# TrinketBlinkM0G.net
KiCad netlist of a schematic drawn in EAGLE
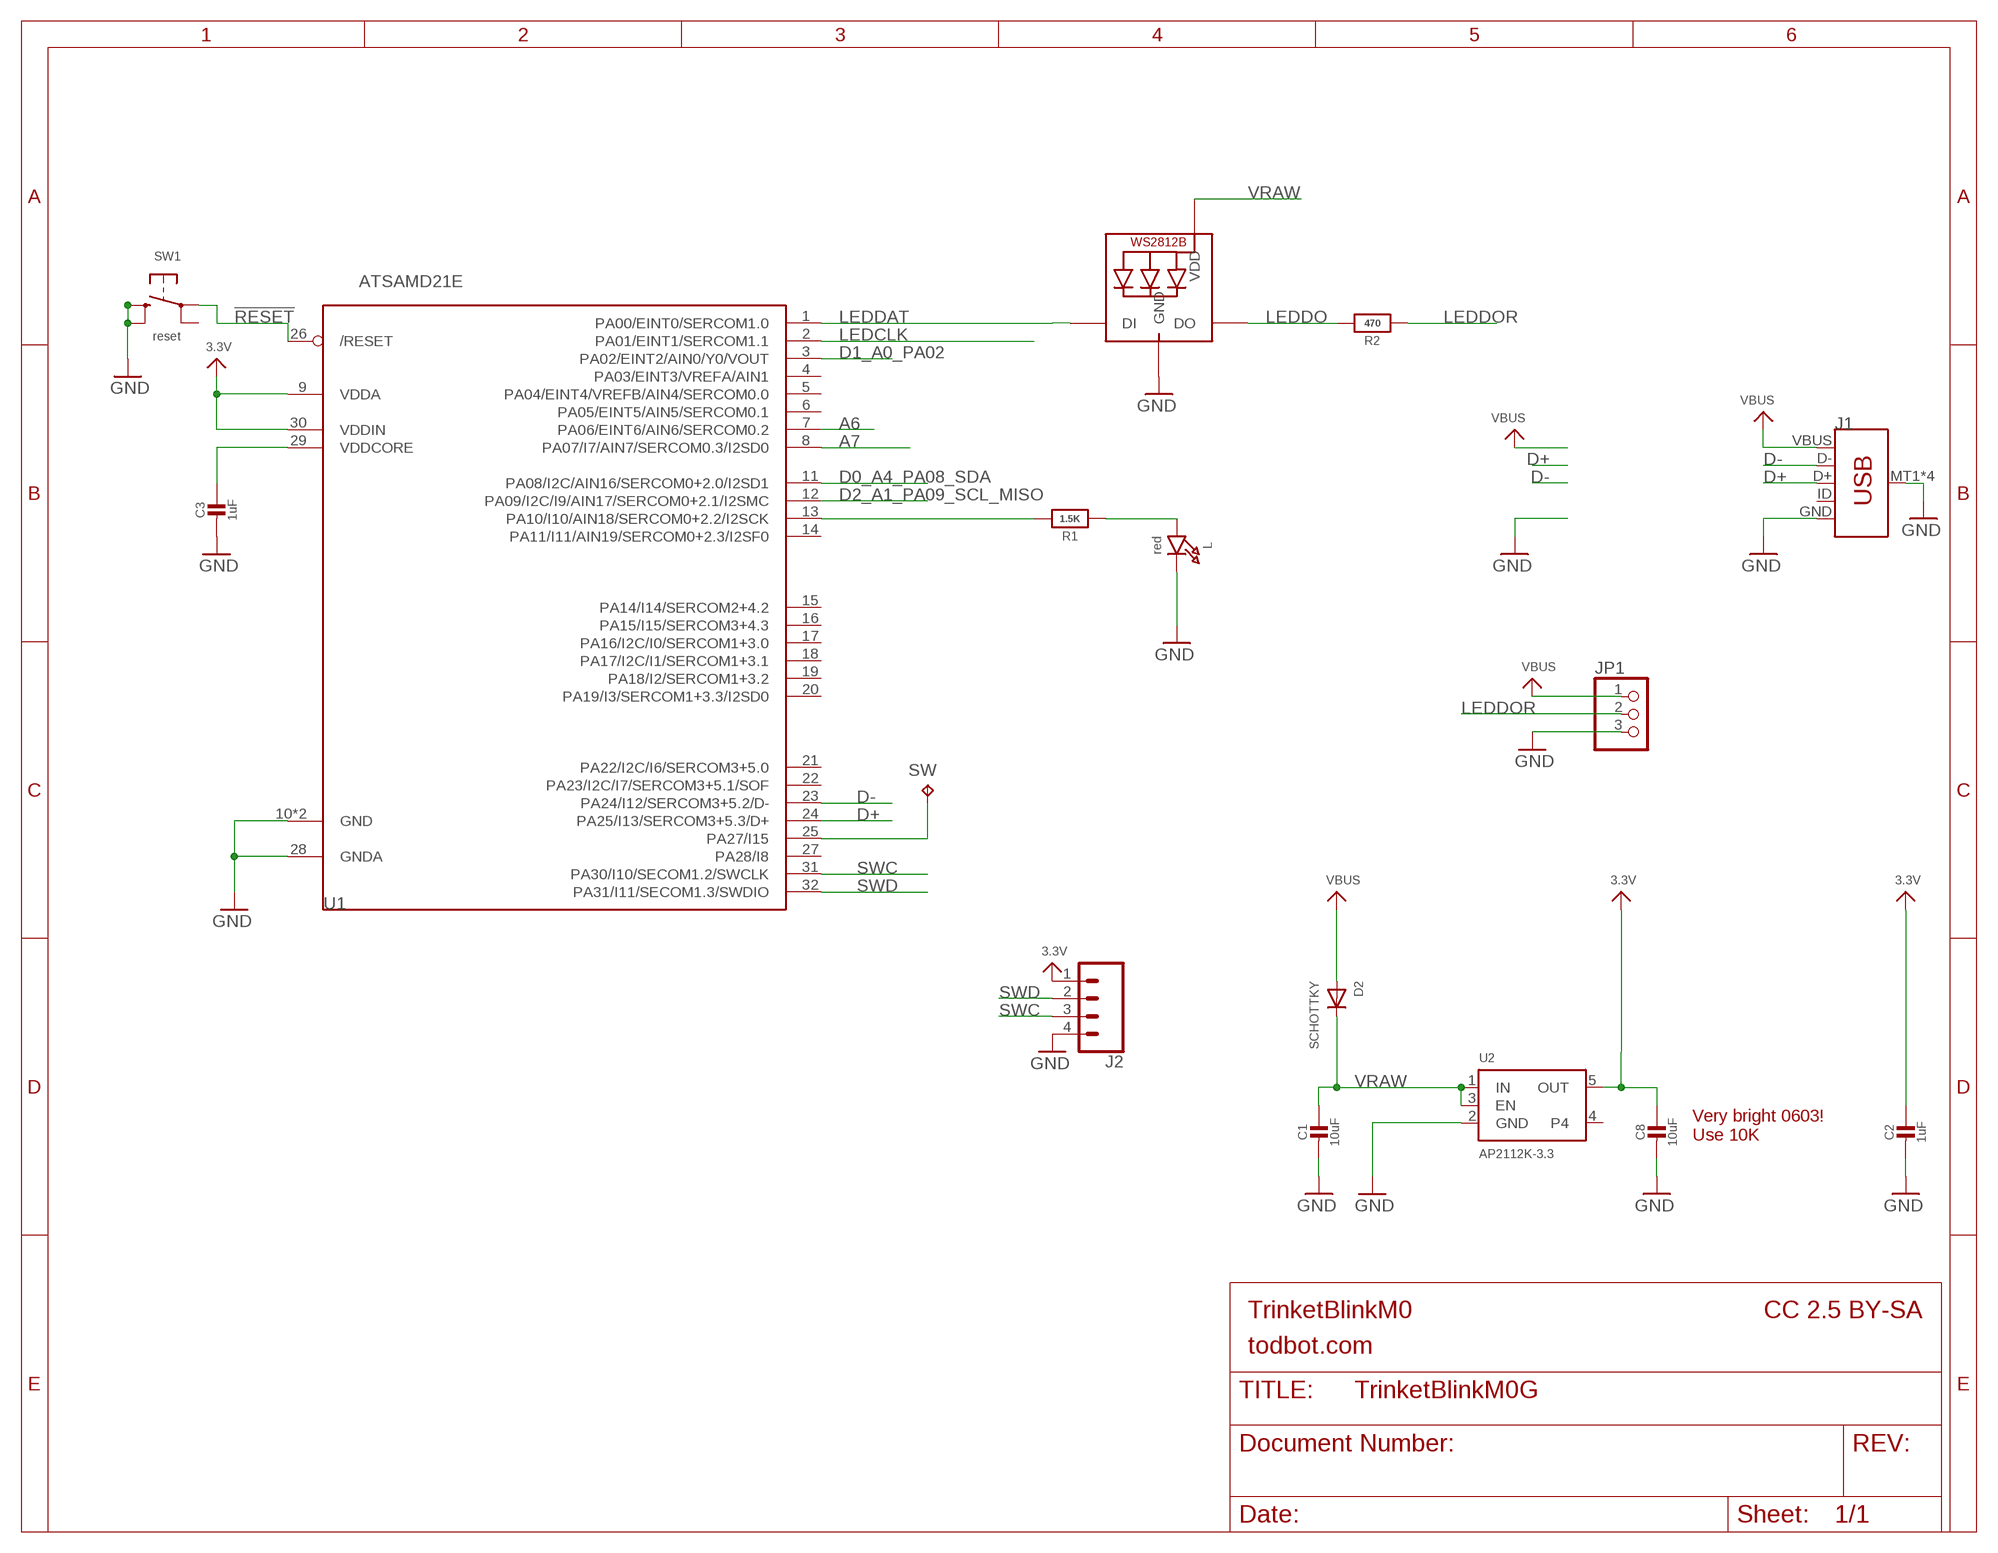
[diagram p0: schematic, sheet 1]

(export (version "E")
  (design (tool "Eeschema 10.0.6"))
  (components
    (comp (ref "C1")
      (value "10uF")
      (footprint "eagle-import:0805-NO")
      (libsource (lib "eagle-import") (part "CAP_CERAMIC0805-NOOUTLINE"))
    )
    (comp (ref "C2")
      (value "1uF")
      (footprint "eagle-import:0603-NO")
      (libsource (lib "eagle-import") (part "CAP_CERAMIC0603_NO"))
    )
    (comp (ref "C3")
      (value "1uF")
      (footprint "eagle-import:0603-NO")
      (libsource (lib "eagle-import") (part "CAP_CERAMIC0603_NO"))
    )
    (comp (ref "C8")
      (value "10uF")
      (footprint "eagle-import:0805-NO")
      (libsource (lib "eagle-import") (part "CAP_CERAMIC0805-NOOUTLINE"))
    )
    (comp (ref "D2")
      (value "SCHOTTKY")
      (footprint "eagle-import:SOD-123FL")
      (libsource (lib "eagle-import") (part "DIODE_SOD-123FL"))
    )
    (comp (ref "J1")
      (value "USB_MICRO-B_SMT")
      (footprint "eagle-import:USB-MICROB")
      (libsource (lib "eagle-import") (part "USB_MICRO-B_SMT"))
    )
    (comp (ref "J2")
      (value "CONN_04")
      (footprint "eagle-import:1X04")
      (libsource (lib "eagle-import") (part "CONN_04"))
    )
    (comp (ref "JP1")
      (value "PINHD-1X3CB")
      (footprint "eagle-import:1X03-CLEANBIG")
      (libsource (lib "eagle-import") (part "PINHD-1X3CB"))
    )
    (comp (ref "L")
      (value "red")
      (footprint "eagle-import:CHIPLED_0603_NOOUTLINE")
      (libsource (lib "eagle-import") (part "LED0603_NOOUTLINE"))
    )
    (comp (ref "LED1")
      (value "WS2812B_5050N")
      (footprint "eagle-import:WS2812B-NARROW")
      (libsource (lib "eagle-import") (part "WS2812B_5050N"))
    )
    (comp (ref "R1")
      (value "1.5K")
      (footprint "eagle-import:0603-NO")
      (libsource (lib "eagle-import") (part "RESISTOR_0603_NOOUT"))
    )
    (comp (ref "R2")
      (value "470")
      (footprint "eagle-import:0603-NO")
      (libsource (lib "eagle-import") (part "RESISTOR_0603_NOOUT"))
    )
    (comp (ref "SW")
      (value "TPB1,27")
      (footprint "eagle-import:B1,27")
      (libsource (lib "eagle-import") (part "TPB1,27"))
    )
    (comp (ref "SW1")
      (value "reset")
      (footprint "eagle-import:BTN_KMR2_4.6X2.8")
      (libsource (lib "eagle-import") (part "SWITCH_TACT_SMT4.6X2.8"))
    )
    (comp (ref "U1")
      (value "ATSAMD21E")
      (footprint "eagle-import:QFN32_5MM")
      (libsource (lib "eagle-import") (part "ATSAMD21E"))
    )
    (comp (ref "U2")
      (value "AP2112K-3.3")
      (footprint "eagle-import:SOT23-5")
      (libsource (lib "eagle-import") (part "VREG_SOT23-5"))
    )
  )
  (nets
    (net (code "1") (name "/A6") (class "Default")
      (node (ref "U1") (pin "7") (pinfunction "PA06/EINT6/AIN6/SERCOM0.2_7") (pintype "bidirectional"))
    )
    (net (code "2") (name "/A7") (class "Default")
      (node (ref "U1") (pin "8") (pinfunction "PA07/I7/AIN7/SERCOM0.3/I2SD0_8") (pintype "bidirectional"))
    )
    (net (code "3") (name "/D+") (class "Default")
      (node (ref "J1") (pin "D+") (pinfunction "D+_D+") (pintype "bidirectional"))
      (node (ref "U1") (pin "24") (pinfunction "PA25/I13/SERCOM3+5.3/D+_24") (pintype "bidirectional"))
    )
    (net (code "4") (name "/D-") (class "Default")
      (node (ref "J1") (pin "D-") (pinfunction "D-_D-") (pintype "bidirectional"))
      (node (ref "U1") (pin "23") (pinfunction "PA24/I12/SERCOM3+5.2/D-_23") (pintype "bidirectional"))
    )
    (net (code "5") (name "/D0_A4_PA08_SDA") (class "Default")
      (node (ref "U1") (pin "11") (pinfunction "PA08/I2C/AIN16/SERCOM0+2.0/I2SD1_11") (pintype "bidirectional"))
    )
    (net (code "6") (name "/D1_A0_PA02") (class "Default")
      (node (ref "U1") (pin "3") (pinfunction "PA02/EINT2/AIN0/Y0/VOUT_3") (pintype "bidirectional"))
    )
    (net (code "7") (name "/D2_A1_PA09_SCL_MISO") (class "Default")
      (node (ref "U1") (pin "12") (pinfunction "PA09/I2C/I9/AIN17/SERCOM0+2.1/I2SMC_12") (pintype "bidirectional"))
    )
    (net (code "8") (name "/LEDCLK") (class "Default")
      (node (ref "U1") (pin "2") (pinfunction "PA01/EINT1/SERCOM1.1_2") (pintype "bidirectional"))
    )
    (net (code "9") (name "/LEDDAT") (class "Default")
      (node (ref "LED1") (pin "4-DIN") (pinfunction "DI_4-DIN") (pintype "input"))
      (node (ref "U1") (pin "1") (pinfunction "PA00/EINT0/SERCOM1.0_1") (pintype "bidirectional"))
    )
    (net (code "10") (name "/LEDDO") (class "Default")
      (node (ref "LED1") (pin "2-DOUT") (pinfunction "DO_2-DOUT") (pintype "output"))
      (node (ref "R2") (pin "2") (pinfunction "2_2") (pintype "passive"))
    )
    (net (code "11") (name "/LEDDOR") (class "Default")
      (node (ref "JP1") (pin "2") (pinfunction "2_2") (pintype "passive"))
      (node (ref "R2") (pin "1") (pinfunction "1_1") (pintype "passive"))
    )
    (net (code "12") (name "/SWC") (class "Default")
      (node (ref "J2") (pin "3") (pinfunction "3_3") (pintype "passive"))
      (node (ref "U1") (pin "31") (pinfunction "PA30/I10/SECOM1.2/SWCLK_31") (pintype "bidirectional"))
    )
    (net (code "13") (name "/SWD") (class "Default")
      (node (ref "J2") (pin "2") (pinfunction "2_2") (pintype "passive"))
      (node (ref "U1") (pin "32") (pinfunction "PA31/I11/SECOM1.3/SWDIO_32") (pintype "bidirectional"))
    )
    (net (code "14") (name "/VRAW") (class "Default")
      (node (ref "C1") (pin "1") (pinfunction "1_1") (pintype "passive"))
      (node (ref "D2") (pin "C") (pinfunction "C_C") (pintype "passive"))
      (node (ref "LED1") (pin "1-VDD") (pinfunction "VDD_1-VDD") (pintype "power_in"))
      (node (ref "U2") (pin "1") (pinfunction "IN_1") (pintype "power_in"))
      (node (ref "U2") (pin "3") (pinfunction "EN_3") (pintype "input"))
    )
    (net (code "15") (name "/~{RESET}") (class "Default")
      (node (ref "SW1") (pin "A") (pinfunction "P_A") (pintype "passive"))
      (node (ref "U1") (pin "26") (pinfunction "/RESET_26") (pintype "bidirectional"))
    )
    (net (code "16") (name "3.3V") (class "Default")
      (node (ref "C2") (pin "1") (pinfunction "1_1") (pintype "passive"))
      (node (ref "C8") (pin "1") (pinfunction "1_1") (pintype "passive"))
      (node (ref "J2") (pin "1") (pinfunction "1_1") (pintype "passive"))
      (node (ref "U1") (pin "30") (pinfunction "VDDIN_30") (pintype "power_in"))
      (node (ref "U1") (pin "9") (pinfunction "VDDA_9") (pintype "power_in"))
      (node (ref "U2") (pin "5") (pinfunction "OUT_5") (pintype "power_in"))
    )
    (net (code "17") (name "GND") (class "Default")
      (node (ref "C1") (pin "2") (pinfunction "2_2") (pintype "passive"))
      (node (ref "C2") (pin "2") (pinfunction "2_2") (pintype "passive"))
      (node (ref "C3") (pin "2") (pinfunction "2_2") (pintype "passive"))
      (node (ref "C8") (pin "2") (pinfunction "2_2") (pintype "passive"))
      (node (ref "J1") (pin "GND") (pinfunction "GND_GND") (pintype "power_in"))
      (node (ref "J1") (pin "MT1") (pinfunction "SHIELD_MT1") (pintype "bidirectional"))
      (node (ref "J1") (pin "MT2") (pinfunction "SHIELD_MT2") (pintype "bidirectional"))
      (node (ref "J1") (pin "P$1") (pinfunction "SHIELD_P$1") (pintype "bidirectional"))
      (node (ref "J1") (pin "P$2") (pinfunction "SHIELD_P$2") (pintype "bidirectional"))
      (node (ref "J2") (pin "4") (pinfunction "4_4") (pintype "passive"))
      (node (ref "JP1") (pin "3") (pinfunction "3_3") (pintype "passive"))
      (node (ref "L") (pin "C") (pinfunction "C_C") (pintype "passive"))
      (node (ref "LED1") (pin "3-GND") (pinfunction "GND_3-GND") (pintype "power_in"))
      (node (ref "SW1") (pin "B") (pinfunction "S_B") (pintype "passive"))
      (node (ref "SW1") (pin "B'") (pinfunction "S1_B'") (pintype "passive"))
      (node (ref "U1") (pin "10") (pinfunction "GND_10") (pintype "power_in"))
      (node (ref "U1") (pin "28") (pinfunction "GNDA_28") (pintype "power_in"))
      (node (ref "U1") (pin "33") (pinfunction "GND_33") (pintype "power_in"))
      (node (ref "U2") (pin "2") (pinfunction "GND_2") (pintype "power_in"))
    )
    (net (code "18") (name "Net-(L-PadA)") (class "Default")
      (node (ref "L") (pin "A") (pinfunction "A_A") (pintype "passive"))
      (node (ref "R1") (pin "1") (pinfunction "1_1") (pintype "passive"))
    )
    (net (code "19") (name "Net-(U1-PA10{slash}I10{slash}AIN18{slash}SERCOM0+2.2{slash}I2SCK)") (class "Default")
      (node (ref "R1") (pin "2") (pinfunction "2_2") (pintype "passive"))
      (node (ref "U1") (pin "13") (pinfunction "PA10/I10/AIN18/SERCOM0+2.2/I2SCK_13") (pintype "bidirectional"))
    )
    (net (code "20") (name "Net-(U1-PA27{slash}I15)") (class "Default")
      (node (ref "SW") (pin "TP") (pinfunction "TP_TP") (pintype "input"))
      (node (ref "U1") (pin "25") (pinfunction "PA27/I15_25") (pintype "bidirectional"))
    )
    (net (code "21") (name "Net-(U1-VDDCORE)") (class "Default")
      (node (ref "C3") (pin "1") (pinfunction "1_1") (pintype "passive"))
      (node (ref "U1") (pin "29") (pinfunction "VDDCORE_29") (pintype "power_in"))
    )
    (net (code "22") (name "VBUS") (class "Default")
      (node (ref "D2") (pin "A") (pinfunction "A_A") (pintype "passive"))
      (node (ref "J1") (pin "VBUS") (pinfunction "VBUS_VBUS") (pintype "power_in"))
      (node (ref "JP1") (pin "1") (pinfunction "1_1") (pintype "passive"))
    )
    (net (code "23") (name "unconnected-(J1-PadID)") (class "Default")
      (node (ref "J1") (pin "ID") (pinfunction "ID_ID") (pintype "bidirectional"))
    )
    (net (code "24") (name "unconnected-(SW1-P1-PadA')") (class "Default")
      (node (ref "SW1") (pin "A'") (pinfunction "P1_A'") (pintype "passive"))
    )
    (net (code "25") (name "unconnected-(U1-PA03{slash}EINT3{slash}VREFA{slash}AIN1-Pad4)") (class "Default")
      (node (ref "U1") (pin "4") (pinfunction "PA03/EINT3/VREFA/AIN1_4") (pintype "bidirectional"))
    )
    (net (code "26") (name "unconnected-(U1-PA04{slash}EINT4{slash}VREFB{slash}AIN4{slash}SERCOM0.0-Pad5)") (class "Default")
      (node (ref "U1") (pin "5") (pinfunction "PA04/EINT4/VREFB/AIN4/SERCOM0.0_5") (pintype "bidirectional"))
    )
    (net (code "27") (name "unconnected-(U1-PA05{slash}EINT5{slash}AIN5{slash}SERCOM0.1-Pad6)") (class "Default")
      (node (ref "U1") (pin "6") (pinfunction "PA05/EINT5/AIN5/SERCOM0.1_6") (pintype "bidirectional"))
    )
    (net (code "28") (name "unconnected-(U1-PA11{slash}I11{slash}AIN19{slash}SERCOM0+2.3{slash}I2SF0-Pad14)") (class "Default")
      (node (ref "U1") (pin "14") (pinfunction "PA11/I11/AIN19/SERCOM0+2.3/I2SF0_14") (pintype "bidirectional"))
    )
    (net (code "29") (name "unconnected-(U1-PA14{slash}I14{slash}SERCOM2+4.2-Pad15)") (class "Default")
      (node (ref "U1") (pin "15") (pinfunction "PA14/I14/SERCOM2+4.2_15") (pintype "bidirectional"))
    )
    (net (code "30") (name "unconnected-(U1-PA15{slash}I15{slash}SERCOM3+4.3-Pad16)") (class "Default")
      (node (ref "U1") (pin "16") (pinfunction "PA15/I15/SERCOM3+4.3_16") (pintype "bidirectional"))
    )
    (net (code "31") (name "unconnected-(U1-PA16{slash}I2C{slash}I0{slash}SERCOM1+3.0-Pad17)") (class "Default")
      (node (ref "U1") (pin "17") (pinfunction "PA16/I2C/I0/SERCOM1+3.0_17") (pintype "bidirectional"))
    )
    (net (code "32") (name "unconnected-(U1-PA17{slash}I2C{slash}I1{slash}SERCOM1+3.1-Pad18)") (class "Default")
      (node (ref "U1") (pin "18") (pinfunction "PA17/I2C/I1/SERCOM1+3.1_18") (pintype "bidirectional"))
    )
    (net (code "33") (name "unconnected-(U1-PA18{slash}I2{slash}SERCOM1+3.2-Pad19)") (class "Default")
      (node (ref "U1") (pin "19") (pinfunction "PA18/I2/SERCOM1+3.2_19") (pintype "bidirectional"))
    )
    (net (code "34") (name "unconnected-(U1-PA19{slash}I3{slash}SERCOM1+3.3{slash}I2SD0-Pad20)") (class "Default")
      (node (ref "U1") (pin "20") (pinfunction "PA19/I3/SERCOM1+3.3/I2SD0_20") (pintype "bidirectional"))
    )
    (net (code "35") (name "unconnected-(U1-PA22{slash}I2C{slash}I6{slash}SERCOM3+5.0-Pad21)") (class "Default")
      (node (ref "U1") (pin "21") (pinfunction "PA22/I2C/I6/SERCOM3+5.0_21") (pintype "bidirectional"))
    )
    (net (code "36") (name "unconnected-(U1-PA23{slash}I2C{slash}I7{slash}SERCOM3+5.1{slash}SOF-Pad22)") (class "Default")
      (node (ref "U1") (pin "22") (pinfunction "PA23/I2C/I7/SERCOM3+5.1/SOF_22") (pintype "bidirectional"))
    )
    (net (code "37") (name "unconnected-(U1-PA28{slash}I8-Pad27)") (class "Default")
      (node (ref "U1") (pin "27") (pinfunction "PA28/I8_27") (pintype "bidirectional"))
    )
    (net (code "38") (name "unconnected-(U2-P4-Pad4)") (class "Default")
      (node (ref "U2") (pin "4") (pinfunction "P4_4") (pintype "bidirectional"))
    )
  )
)
